# Sheet1.net
KiCad netlist of a schematic drawn in Altium Designer
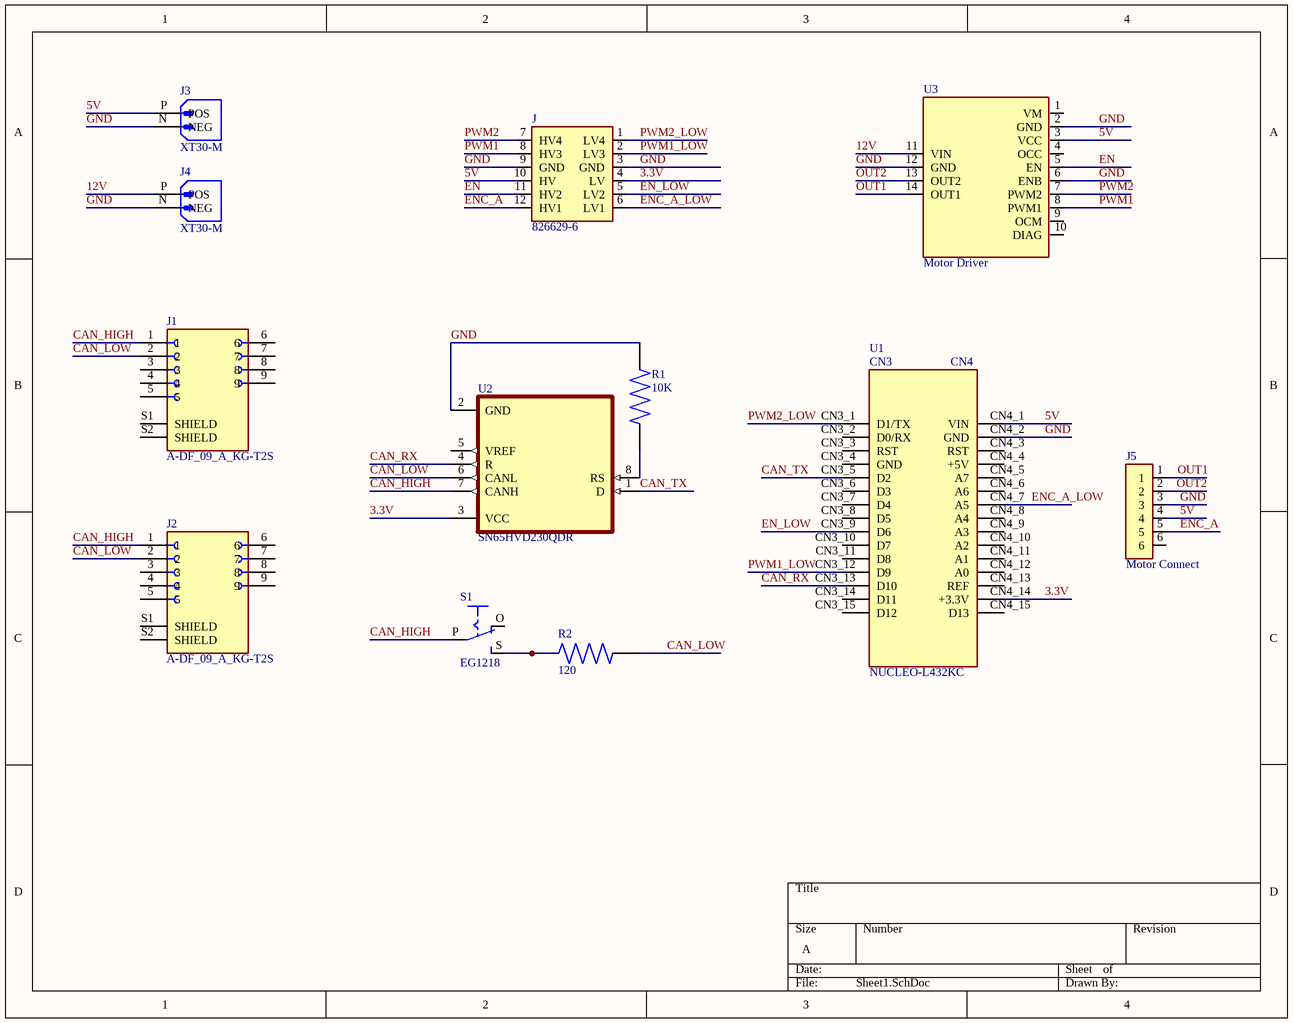
[diagram p0: Sheet1.SchDoc]

(export (version "E")
  (design (tool "Eeschema 10.0.6"))
  (components
    (comp (ref "J")
      (value "826629-6")
      (footprint "Level Converter:HDRV6W63P254_6X1_1524X250X950")
      (description "Conn Unshrouded Header HDR 6 POS 2.54mm Solder ST Thru-Hole Automotive Carton")
      (fields (field (name "MF") "TE Connectivity"))
      (libsource (lib "Level Converter") (part "826629-6"))
    )
    (comp (ref "J1")
      (value "A-DF_09_A_KG-T2S")
      (footprint "ASSMANN_A-DF_09_A_KG-T2S")
      (description "9 Position D-Sub Receptacle, Female Sockets Connector")
      (fields (field (name "MF") "Assmann WSW") (field (name "MP") "A-DF 09 A/KG-T2S"))
      (libsource (lib "A-DF_09_A_KG-T2S") (part "A-DF_09_A_KG-T2S"))
    )
    (comp (ref "J2")
      (value "A-DF_09_A_KG-T2S")
      (footprint "ASSMANN_A-DF_09_A_KG-T2S")
      (description "9 Position D-Sub Receptacle, Female Sockets Connector")
      (fields (field (name "MF") "Assmann WSW") (field (name "MP") "A-DF 09 A/KG-T2S"))
      (libsource (lib "A-DF_09_A_KG-T2S") (part "A-DF_09_A_KG-T2S"))
    )
    (comp (ref "J3")
      (value "XT30-M")
      (footprint "AMASS_XT60-M")
      (description "Plug; DC supply; XT60; male; PIN: 2; for cable; soldered; 30A; 500V")
      (fields (field (name "MP") "XT60-M") (field (name "MF") "AMASS"))
      (libsource (lib "XT30-M") (part "XT30-M"))
    )
    (comp (ref "J4")
      (value "XT30-M")
      (footprint "AMASS_XT60-M")
      (description "Plug; DC supply; XT60; male; PIN: 2; for cable; soldered; 30A; 500V")
      (fields (field (name "MP") "XT60-M") (field (name "MF") "AMASS"))
      (libsource (lib "XT30-M") (part "XT30-M"))
    )
    (comp (ref "J5")
      (value "Motor Connect")
      (footprint "HDRV6W63P254_6X1_1524X250X950")
      (description "Conn Unshrouded Header HDR 6 POS 2.54mm Solder ST Thru-Hole Automotive Carton")
      (fields (field (name "MP") "826629-6") (field (name "MF") "TE Connectivity"))
      (libsource (lib "826629-6") (part "826629-6"))
    )
    (comp (ref "R1")
      (value "10K")
      (footprint "RESC3216X65N:RESC3216X65N")
      (fields (field (name "MP") "KTR18EZPF9530"))
      (libsource (lib "KTR18EZPF9530") (part "KTR18EZPF9530"))
    )
    (comp (ref "R2")
      (value "120")
      (footprint "RESC3216X65N:RESC3216X65N")
      (fields (field (name "MP") "KTR18EZPF9530"))
      (libsource (lib "KTR18EZPF9530") (part "KTR18EZPF9530"))
    )
    (comp (ref "S1") (value "EG1218") (footprint "EG1218:EG1218") (libsource (lib "EG1218") (part "EG1218")))
    (comp (ref "U1")
      (value "NUCLEO-L432KC")
      (footprint "MODULE_NUCLEO-L432KC")
      (description "STM32 Nucleo-32 development board with STM32L432KC MCU, supports Arduino connectivity")
      (libsource (lib "NUCLEO-L432KC") (part "NUCLEO-L432KC"))
    )
    (comp (ref "U2")
      (value "SN65HVD230QDR")
      (footprint "SOIC127P599X175-8N")
      (description "3.3-V CAN Transceiver with Standby Mode 8-SOIC -40 to 125")
      (fields (field (name "MF") "Texas Instruments"))
      (libsource (lib "SN65HVD230QDR") (part "SN65HVD230QDR"))
    )
    (comp (ref "U3")
      (value "Motor Driver")
      (footprint "SnapEDApcb:TE_826629-8")
      (description "Conn Unshrouded Header HDR 8 POS 2.54mm Solder ST Thru-Hole Automotive Box")
      (fields (field (name "MP") "826629-8") (field (name "MF") "TE Connectivity"))
      (libsource (lib "Pololu Motor Driver") (part "826629-8"))
    )
  )
  (nets
    (net (code "1") (name "/3.3V") (class "Default")
      (node (ref "J") (pin "4") (pinfunction "LV_4") (pintype "passive"))
      (node (ref "U1") (pin "CN4_14") (pinfunction "+3.3V_CN4_14") (pintype "power_in"))
      (node (ref "U2") (pin "3") (pinfunction "VCC_3") (pintype "power_in"))
    )
    (net (code "2") (name "/5V") (class "Default")
      (node (ref "J") (pin "10") (pinfunction "HV_10") (pintype "passive"))
      (node (ref "J3") (pin "P") (pinfunction "POS_P") (pintype "passive"))
      (node (ref "J5") (pin "4") (pinfunction "4_4") (pintype "passive"))
      (node (ref "U1") (pin "CN4_1") (pinfunction "VIN_CN4_1") (pintype "power_in"))
      (node (ref "U3") (pin "3") (pinfunction "VCC_3") (pintype "passive"))
    )
    (net (code "3") (name "/12V") (class "Default")
      (node (ref "J4") (pin "P") (pinfunction "POS_P") (pintype "passive"))
      (node (ref "U3") (pin "11") (pinfunction "VIN_11") (pintype "passive"))
    )
    (net (code "4") (name "/CAN_HIGH") (class "Default")
      (node (ref "J1") (pin "1") (pinfunction "1_1") (pintype "passive"))
      (node (ref "J2") (pin "1") (pinfunction "1_1") (pintype "passive"))
      (node (ref "S1") (pin "P") (pinfunction "P_P") (pintype "passive"))
      (node (ref "U2") (pin "7") (pinfunction "CANH_7") (pintype "output"))
    )
    (net (code "5") (name "/CAN_LOW") (class "Default")
      (node (ref "J1") (pin "2") (pinfunction "2_2") (pintype "passive"))
      (node (ref "J2") (pin "2") (pinfunction "2_2") (pintype "passive"))
      (node (ref "R2") (pin "1") (pinfunction "1_1") (pintype "passive"))
      (node (ref "U2") (pin "6") (pinfunction "CANL_6") (pintype "output"))
    )
    (net (code "6") (name "/CAN_RX") (class "Default")
      (node (ref "U1") (pin "CN3_13") (pinfunction "D10_CN3_13") (pintype "passive"))
      (node (ref "U2") (pin "4") (pinfunction "R_4") (pintype "output"))
    )
    (net (code "7") (name "/CAN_TX") (class "Default")
      (node (ref "U1") (pin "CN3_5") (pinfunction "D2_CN3_5") (pintype "power_in"))
      (node (ref "U2") (pin "1") (pinfunction "D_1") (pintype "input"))
    )
    (net (code "8") (name "/EN") (class "Default")
      (node (ref "J") (pin "11") (pinfunction "HV2_11") (pintype "passive"))
      (node (ref "U3") (pin "5") (pinfunction "EN_5") (pintype "passive"))
    )
    (net (code "9") (name "/ENC_A") (class "Default")
      (node (ref "J") (pin "12") (pinfunction "HV1_12") (pintype "passive"))
      (node (ref "J5") (pin "5") (pinfunction "5_5") (pintype "passive"))
    )
    (net (code "10") (name "/ENC_A_LOW") (class "Default")
      (node (ref "J") (pin "6") (pinfunction "LV1_6") (pintype "passive"))
      (node (ref "U1") (pin "CN4_7") (pinfunction "A5_CN4_7") (pintype "passive"))
    )
    (net (code "11") (name "/EN_LOW") (class "Default")
      (node (ref "J") (pin "5") (pinfunction "LV2_5") (pintype "passive"))
      (node (ref "U1") (pin "CN3_9") (pinfunction "D6_CN3_9") (pintype "power_in"))
    )
    (net (code "12") (name "/GND") (class "Default")
      (node (ref "J") (pin "3") (pinfunction "GND_3") (pintype "passive"))
      (node (ref "J") (pin "9") (pinfunction "GND_9") (pintype "passive"))
      (node (ref "J3") (pin "N") (pinfunction "NEG_N") (pintype "passive"))
      (node (ref "J4") (pin "N") (pinfunction "NEG_N") (pintype "passive"))
      (node (ref "J5") (pin "3") (pinfunction "3_3") (pintype "passive"))
      (node (ref "R1") (pin "2") (pinfunction "2_2") (pintype "passive"))
      (node (ref "U1") (pin "CN4_2") (pinfunction "GND_CN4_2") (pintype "power_in"))
      (node (ref "U2") (pin "2") (pinfunction "GND_2") (pintype "power_in"))
      (node (ref "U3") (pin "12") (pinfunction "GND_12") (pintype "passive"))
      (node (ref "U3") (pin "2") (pinfunction "GND_2") (pintype "passive"))
      (node (ref "U3") (pin "6") (pinfunction "ENB_6") (pintype "passive"))
    )
    (net (code "13") (name "/OUT1") (class "Default")
      (node (ref "J5") (pin "1") (pinfunction "1_1") (pintype "passive"))
      (node (ref "U3") (pin "14") (pinfunction "OUT1_14") (pintype "passive"))
    )
    (net (code "14") (name "/OUT2") (class "Default")
      (node (ref "J5") (pin "2") (pinfunction "2_2") (pintype "passive"))
      (node (ref "U3") (pin "13") (pinfunction "OUT2_13") (pintype "passive"))
    )
    (net (code "15") (name "/PWM1") (class "Default")
      (node (ref "J") (pin "8") (pinfunction "HV3_8") (pintype "passive"))
      (node (ref "U3") (pin "8") (pinfunction "PWM1_8") (pintype "passive"))
    )
    (net (code "16") (name "/PWM1_LOW") (class "Default")
      (node (ref "J") (pin "2") (pinfunction "LV3_2") (pintype "passive"))
      (node (ref "U1") (pin "CN3_12") (pinfunction "D9_CN3_12") (pintype "power_in"))
    )
    (net (code "17") (name "/PWM2") (class "Default")
      (node (ref "J") (pin "7") (pinfunction "HV4_7") (pintype "passive"))
      (node (ref "U3") (pin "7") (pinfunction "PWM2_7") (pintype "passive"))
    )
    (net (code "18") (name "/PWM2_LOW") (class "Default")
      (node (ref "J") (pin "1") (pinfunction "LV4_1") (pintype "passive"))
      (node (ref "U1") (pin "CN3_1") (pinfunction "D1/TX_CN3_1") (pintype "power_in"))
    )
    (net (code "19") (name "Net-(R2-Pad2)") (class "Default")
      (node (ref "R2") (pin "2") (pinfunction "2_2") (pintype "passive"))
      (node (ref "S1") (pin "S") (pinfunction "S_S") (pintype "passive"))
    )
    (net (code "20") (name "Net-(U2-RS)") (class "Default")
      (node (ref "R1") (pin "1") (pinfunction "1_1") (pintype "passive"))
      (node (ref "U2") (pin "8") (pinfunction "RS_8") (pintype "input"))
    )
    (net (code "21") (name "unconnected-(J1-Pad3)") (class "Default")
      (node (ref "J1") (pin "3") (pinfunction "3_3") (pintype "passive"))
    )
    (net (code "22") (name "unconnected-(J1-Pad4)") (class "Default")
      (node (ref "J1") (pin "4") (pinfunction "4_4") (pintype "passive"))
    )
    (net (code "23") (name "unconnected-(J1-Pad5)") (class "Default")
      (node (ref "J1") (pin "5") (pinfunction "5_5") (pintype "passive"))
    )
    (net (code "24") (name "unconnected-(J1-Pad6)") (class "Default")
      (node (ref "J1") (pin "6") (pinfunction "6_6") (pintype "passive"))
    )
    (net (code "25") (name "unconnected-(J1-Pad7)") (class "Default")
      (node (ref "J1") (pin "7") (pinfunction "7_7") (pintype "passive"))
    )
    (net (code "26") (name "unconnected-(J1-Pad8)") (class "Default")
      (node (ref "J1") (pin "8") (pinfunction "8_8") (pintype "passive"))
    )
    (net (code "27") (name "unconnected-(J1-Pad9)") (class "Default")
      (node (ref "J1") (pin "9") (pinfunction "9_9") (pintype "passive"))
    )
    (net (code "28") (name "unconnected-(J1-SHIELD-PadS1)") (class "Default")
      (node (ref "J1") (pin "S1") (pinfunction "SHIELD_S1") (pintype "passive"))
    )
    (net (code "29") (name "unconnected-(J1-SHIELD-PadS2)") (class "Default")
      (node (ref "J1") (pin "S2") (pinfunction "SHIELD_S2") (pintype "passive"))
    )
    (net (code "30") (name "unconnected-(J2-Pad3)") (class "Default")
      (node (ref "J2") (pin "3") (pinfunction "3_3") (pintype "passive"))
    )
    (net (code "31") (name "unconnected-(J2-Pad4)") (class "Default")
      (node (ref "J2") (pin "4") (pinfunction "4_4") (pintype "passive"))
    )
    (net (code "32") (name "unconnected-(J2-Pad5)") (class "Default")
      (node (ref "J2") (pin "5") (pinfunction "5_5") (pintype "passive"))
    )
    (net (code "33") (name "unconnected-(J2-Pad6)") (class "Default")
      (node (ref "J2") (pin "6") (pinfunction "6_6") (pintype "passive"))
    )
    (net (code "34") (name "unconnected-(J2-Pad7)") (class "Default")
      (node (ref "J2") (pin "7") (pinfunction "7_7") (pintype "passive"))
    )
    (net (code "35") (name "unconnected-(J2-Pad8)") (class "Default")
      (node (ref "J2") (pin "8") (pinfunction "8_8") (pintype "passive"))
    )
    (net (code "36") (name "unconnected-(J2-Pad9)") (class "Default")
      (node (ref "J2") (pin "9") (pinfunction "9_9") (pintype "passive"))
    )
    (net (code "37") (name "unconnected-(J2-SHIELD-PadS1)") (class "Default")
      (node (ref "J2") (pin "S1") (pinfunction "SHIELD_S1") (pintype "passive"))
    )
    (net (code "38") (name "unconnected-(J2-SHIELD-PadS2)") (class "Default")
      (node (ref "J2") (pin "S2") (pinfunction "SHIELD_S2") (pintype "passive"))
    )
    (net (code "39") (name "unconnected-(J5-Pad6)") (class "Default")
      (node (ref "J5") (pin "6") (pinfunction "6_6") (pintype "passive"))
    )
    (net (code "40") (name "unconnected-(S1-PadO)") (class "Default")
      (node (ref "S1") (pin "O") (pinfunction "O_O") (pintype "passive"))
    )
    (net (code "41") (name "unconnected-(U1-+5V-PadCN4_4)") (class "Default")
      (node (ref "U1") (pin "CN4_4") (pinfunction "+5V_CN4_4") (pintype "power_in"))
    )
    (net (code "42") (name "unconnected-(U1-A0-PadCN4_12)") (class "Default")
      (node (ref "U1") (pin "CN4_12") (pinfunction "A0_CN4_12") (pintype "passive"))
    )
    (net (code "43") (name "unconnected-(U1-A1-PadCN4_11)") (class "Default")
      (node (ref "U1") (pin "CN4_11") (pinfunction "A1_CN4_11") (pintype "passive"))
    )
    (net (code "44") (name "unconnected-(U1-A2-PadCN4_10)") (class "Default")
      (node (ref "U1") (pin "CN4_10") (pinfunction "A2_CN4_10") (pintype "passive"))
    )
    (net (code "45") (name "unconnected-(U1-A3-PadCN4_9)") (class "Default")
      (node (ref "U1") (pin "CN4_9") (pinfunction "A3_CN4_9") (pintype "passive"))
    )
    (net (code "46") (name "unconnected-(U1-A4-PadCN4_8)") (class "Default")
      (node (ref "U1") (pin "CN4_8") (pinfunction "A4_CN4_8") (pintype "passive"))
    )
    (net (code "47") (name "unconnected-(U1-A6-PadCN4_6)") (class "Default")
      (node (ref "U1") (pin "CN4_6") (pinfunction "A6_CN4_6") (pintype "passive"))
    )
    (net (code "48") (name "unconnected-(U1-A7-PadCN4_5)") (class "Default")
      (node (ref "U1") (pin "CN4_5") (pinfunction "A7_CN4_5") (pintype "passive"))
    )
    (net (code "49") (name "unconnected-(U1-D0{slash}RX-PadCN3_2)") (class "Default")
      (node (ref "U1") (pin "CN3_2") (pinfunction "D0/RX_CN3_2") (pintype "power_in"))
    )
    (net (code "50") (name "unconnected-(U1-D3-PadCN3_6)") (class "Default")
      (node (ref "U1") (pin "CN3_6") (pinfunction "D3_CN3_6") (pintype "power_in"))
    )
    (net (code "51") (name "unconnected-(U1-D4-PadCN3_7)") (class "Default")
      (node (ref "U1") (pin "CN3_7") (pinfunction "D4_CN3_7") (pintype "power_in"))
    )
    (net (code "52") (name "unconnected-(U1-D5-PadCN3_8)") (class "Default")
      (node (ref "U1") (pin "CN3_8") (pinfunction "D5_CN3_8") (pintype "power_in"))
    )
    (net (code "53") (name "unconnected-(U1-D7-PadCN3_10)") (class "Default")
      (node (ref "U1") (pin "CN3_10") (pinfunction "D7_CN3_10") (pintype "power_in"))
    )
    (net (code "54") (name "unconnected-(U1-D8-PadCN3_11)") (class "Default")
      (node (ref "U1") (pin "CN3_11") (pinfunction "D8_CN3_11") (pintype "power_in"))
    )
    (net (code "55") (name "unconnected-(U1-D11-PadCN3_14)") (class "Default")
      (node (ref "U1") (pin "CN3_14") (pinfunction "D11_CN3_14") (pintype "power_in"))
    )
    (net (code "56") (name "unconnected-(U1-D12-PadCN3_15)") (class "Default")
      (node (ref "U1") (pin "CN3_15") (pinfunction "D12_CN3_15") (pintype "power_in"))
    )
    (net (code "57") (name "unconnected-(U1-D13-PadCN4_15)") (class "Default")
      (node (ref "U1") (pin "CN4_15") (pinfunction "D13_CN4_15") (pintype "power_in"))
    )
    (net (code "58") (name "unconnected-(U1-GND-PadCN3_4)") (class "Default")
      (node (ref "U1") (pin "CN3_4") (pinfunction "GND_CN3_4") (pintype "power_in"))
    )
    (net (code "59") (name "unconnected-(U1-REF-PadCN4_13)") (class "Default")
      (node (ref "U1") (pin "CN4_13") (pinfunction "REF_CN4_13") (pintype "passive"))
    )
    (net (code "60") (name "unconnected-(U1-RST-PadCN3_3)") (class "Default")
      (node (ref "U1") (pin "CN3_3") (pinfunction "RST_CN3_3") (pintype "power_in"))
    )
    (net (code "61") (name "unconnected-(U1-RST-PadCN4_3)") (class "Default")
      (node (ref "U1") (pin "CN4_3") (pinfunction "RST_CN4_3") (pintype "passive"))
    )
    (net (code "62") (name "unconnected-(U2-VREF-Pad5)") (class "Default")
      (node (ref "U2") (pin "5") (pinfunction "VREF_5") (pintype "output"))
    )
    (net (code "63") (name "unconnected-(U3-DIAG-Pad10)") (class "Default")
      (node (ref "U3") (pin "10") (pinfunction "DIAG_10") (pintype "passive"))
    )
    (net (code "64") (name "unconnected-(U3-OCC-Pad4)") (class "Default")
      (node (ref "U3") (pin "4") (pinfunction "OCC_4") (pintype "passive"))
    )
    (net (code "65") (name "unconnected-(U3-OCM-Pad9)") (class "Default")
      (node (ref "U3") (pin "9") (pinfunction "OCM_9") (pintype "passive"))
    )
    (net (code "66") (name "unconnected-(U3-VM-Pad1)") (class "Default")
      (node (ref "U3") (pin "1") (pinfunction "VM_1") (pintype "passive"))
    )
  )
)
